# design.net
KiCad netlist of a schematic drawn in Altium Designer
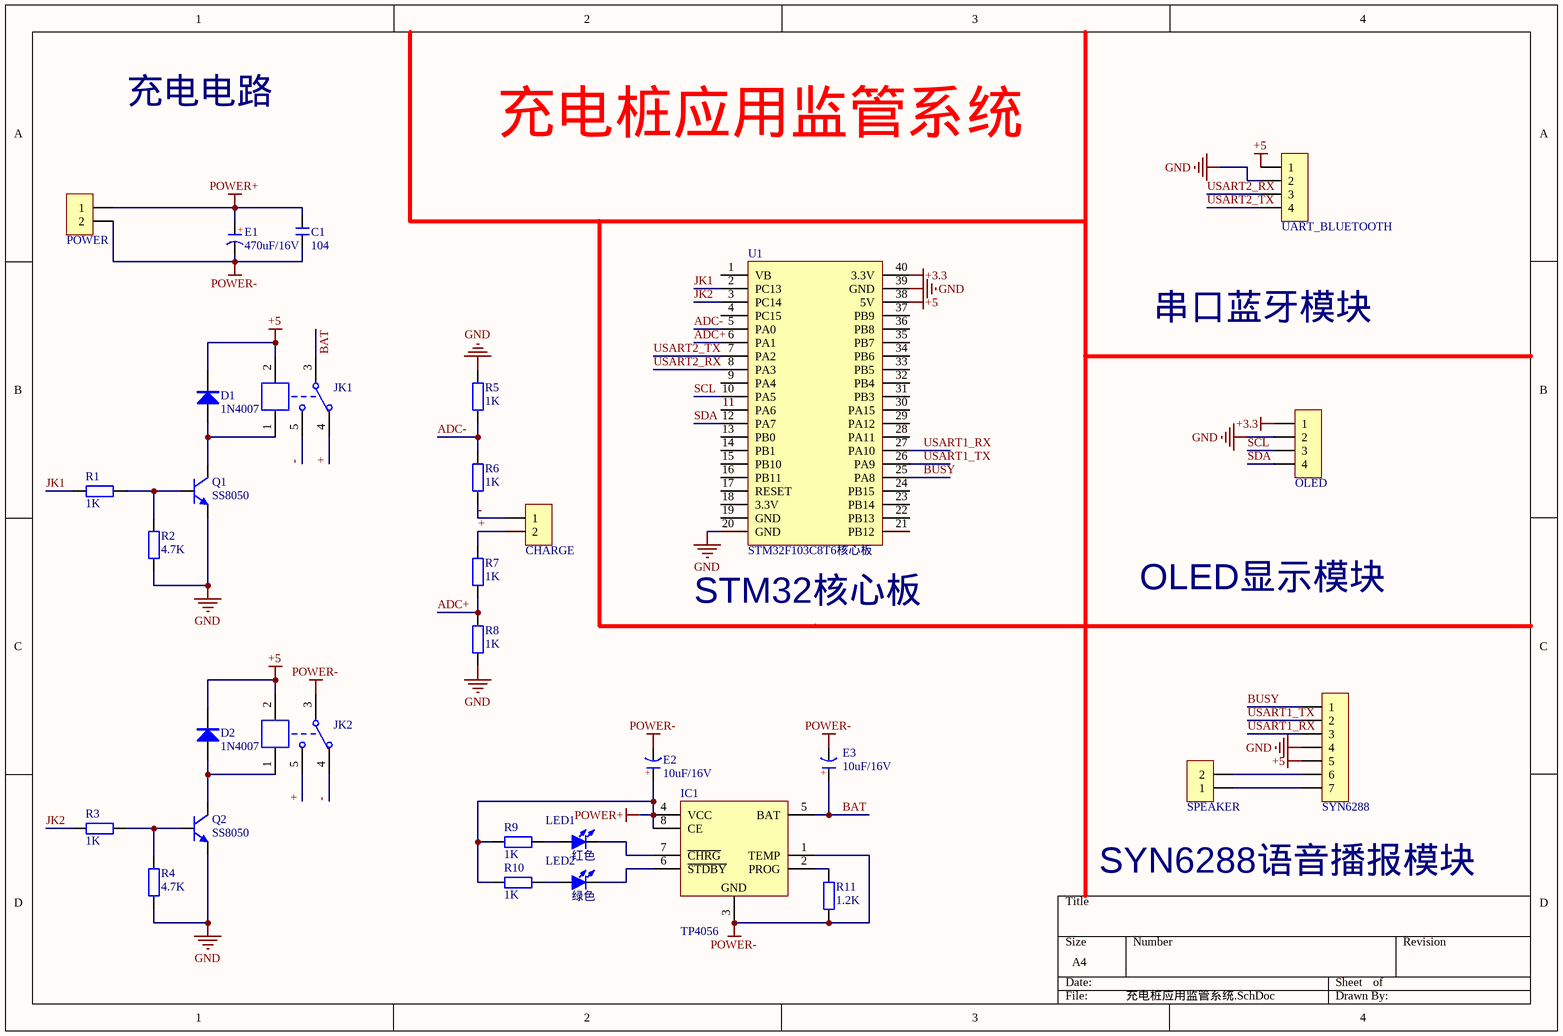
[diagram p0: 充电桩应用监管系统.SchDoc]

(export (version "E")
  (design (tool "Eeschema 10.0.6"))
  (components
    (comp (ref "C1")
      (value "104")
      (footprint "CC 1.8*3.6")
      (description "直插瓷片电容")
      (fields (field (name "版权归属") "源创客"))
      (libsource (lib "3.1   - 电阻-电容-电感") (part "C-CC"))
    )
    (comp (ref "CHARGE")
      (value "HDR-1X2")
      (footprint "KF301-5.0-2P")
      (description "2P接插件")
      (fields (field (name "版权归属") "源创客"))
      (libsource (lib "4.9   - 接插件-脚距5.0") (part "Header 2"))
    )
    (comp (ref "D1")
      (value "1N4007")
      (footprint "DO-41")
      (description "整流二极管")
      (fields (field (name "版权归属") "源创客"))
      (libsource (lib "8.1   - 二极管-整流桥") (part "1N4007"))
    )
    (comp (ref "D2")
      (value "1N4007")
      (footprint "DO-41")
      (description "整流二极管")
      (fields (field (name "版权归属") "源创客"))
      (libsource (lib "8.1   - 二极管-整流桥") (part "1N4007"))
    )
    (comp (ref "E1")
      (value "470uF/16V")
      (footprint "CAP 2.0*5*11")
      (description "直插电解电容")
      (fields (field (name "版权归属") "源创客"))
      (libsource (lib "3.1   - 电阻-电容-电感") (part "C-CAP"))
    )
    (comp (ref "E2")
      (value "10uF/16V")
      (footprint "CAP 1.5*4*8")
      (description "直插电解电容")
      (fields (field (name "版权归属") "源创客"))
      (libsource (lib "3.1   - 电阻-电容-电感") (part "C-CAP"))
    )
    (comp (ref "E3")
      (value "10uF/16V")
      (footprint "CAP 1.5*4*8")
      (description "直插电解电容")
      (fields (field (name "版权归属") "源创客"))
      (libsource (lib "3.1   - 电阻-电容-电感") (part "C-CAP"))
    )
    (comp (ref "IC1")
      (value "TP4056")
      (footprint "SOP8_N")
      (description "锂电池充电管理")
      (fields (field (name "版权归属") "源创客"))
      (libsource (lib "1.3   - 电源类芯片") (part "TP4056"))
    )
    (comp (ref "JK1")
      (value "~")
      (footprint "SRD-C_B")
      (description "5V一组转换")
      (fields (field (name "版权归属") "源创客"))
      (libsource (lib "7.1   - 继电器") (part "SRD-05VDC-SL-C"))
    )
    (comp (ref "JK2")
      (value "~")
      (footprint "SRD-C_B")
      (description "5V一组转换")
      (fields (field (name "版权归属") "源创客"))
      (libsource (lib "7.1   - 继电器") (part "SRD-05VDC-SL-C"))
    )
    (comp (ref "LED1")
      (value "红色")
      (footprint "LED 3MM-B")
      (description "插件LED")
      (fields (field (name "版权归属") "源创客"))
      (libsource (lib "9.1   - LED") (part "LED-3MM"))
    )
    (comp (ref "LED2")
      (value "绿色")
      (footprint "LED 3MM-B")
      (description "插件LED")
      (fields (field (name "版权归属") "源创客"))
      (libsource (lib "9.1   - LED") (part "LED-3MM"))
    )
    (comp (ref "OLED")
      (value "HDR-1X4")
      (footprint "HDR2.54-M-LI-4P")
      (description "4P接插件")
      (fields (field (name "版权归属") "源创客"))
      (libsource (lib "4.5   - 接插件-脚距2.54") (part "Header 4"))
    )
    (comp (ref "POWER")
      (value "HDR-1X2")
      (footprint "KF301-5.0-2P")
      (description "2P接插件")
      (fields (field (name "版权归属") "源创客"))
      (libsource (lib "") (part "Header 2_1"))
    )
    (comp (ref "Q1")
      (value "SS8050")
      (footprint "TO92A")
      (description "高频放大-NPN型")
      (fields (field (name "版权归属") "源创客"))
      (libsource (lib "6.2   - 三极管") (part "8050-DIP"))
    )
    (comp (ref "Q2")
      (value "SS8050")
      (footprint "TO92A")
      (description "高频放大-NPN型")
      (fields (field (name "版权归属") "源创客"))
      (libsource (lib "6.2   - 三极管") (part "8050-DIP"))
    )
    (comp (ref "R1")
      (value "1K")
      (footprint "RS 1/4W")
      (description "直插色环电阻")
      (fields (field (name "版权归属") "源创客"))
      (libsource (lib "3.1   - 电阻-电容-电感") (part "R-CRR"))
    )
    (comp (ref "R2")
      (value "4.7K")
      (footprint "RS 1/4W")
      (description "直插色环电阻")
      (fields (field (name "版权归属") "源创客"))
      (libsource (lib "3.1   - 电阻-电容-电感") (part "R-CRR"))
    )
    (comp (ref "R3")
      (value "1K")
      (footprint "RS 1/4W")
      (description "直插色环电阻")
      (fields (field (name "版权归属") "源创客"))
      (libsource (lib "3.1   - 电阻-电容-电感") (part "R-CRR"))
    )
    (comp (ref "R4")
      (value "4.7K")
      (footprint "RS 1/4W")
      (description "直插色环电阻")
      (fields (field (name "版权归属") "源创客"))
      (libsource (lib "3.1   - 电阻-电容-电感") (part "R-CRR"))
    )
    (comp (ref "R5")
      (value "1K")
      (footprint "RS 1/4W")
      (description "直插色环电阻")
      (fields (field (name "版权归属") "源创客"))
      (libsource (lib "3.1   - 电阻-电容-电感") (part "R-CRR"))
    )
    (comp (ref "R6")
      (value "1K")
      (footprint "RS 1/4W")
      (description "直插色环电阻")
      (fields (field (name "版权归属") "源创客"))
      (libsource (lib "3.1   - 电阻-电容-电感") (part "R-CRR"))
    )
    (comp (ref "R7")
      (value "1K")
      (footprint "RS 1/4W")
      (description "直插色环电阻")
      (fields (field (name "版权归属") "源创客"))
      (libsource (lib "3.1   - 电阻-电容-电感") (part "R-CRR"))
    )
    (comp (ref "R8")
      (value "1K")
      (footprint "RS 1/4W")
      (description "直插色环电阻")
      (fields (field (name "版权归属") "源创客"))
      (libsource (lib "3.1   - 电阻-电容-电感") (part "R-CRR"))
    )
    (comp (ref "R9")
      (value "1K")
      (footprint "RS 1/4W")
      (description "直插色环电阻")
      (fields (field (name "版权归属") "源创客"))
      (libsource (lib "3.1   - 电阻-电容-电感") (part "R-CRR"))
    )
    (comp (ref "R10")
      (value "1K")
      (footprint "RS 1/4W")
      (description "直插色环电阻")
      (fields (field (name "版权归属") "源创客"))
      (libsource (lib "3.1   - 电阻-电容-电感") (part "R-CRR"))
    )
    (comp (ref "R11")
      (value "1.2K")
      (footprint "RS 1/4W")
      (description "直插色环电阻")
      (fields (field (name "版权归属") "源创客"))
      (libsource (lib "3.1   - 电阻-电容-电感") (part "R-CRR"))
    )
    (comp (ref "SPEAKER")
      (value "HDR-1X2")
      (footprint "KF301-5.0-2P")
      (description "2P接插件")
      (fields (field (name "版权归属") "源创客"))
      (libsource (lib "") (part "Header 2_2"))
    )
    (comp (ref "SYN6288")
      (value "HDR-1X7")
      (footprint "PH2.0-LI-7P")
      (description "7P接插件")
      (fields (field (name "版权归属") "源创客"))
      (libsource (lib "4.4   - 接插件-脚距2.0") (part "Header 7"))
    )
    (comp (ref "U1")
      (value "STM32F103C8T6核心板")
      (footprint "DIP_TP40-600")
      (libsource (lib "STM32F103C8T6核心板") (part "STM32F103C8T6核心板"))
    )
    (comp (ref "UART_BLUETOOTH")
      (value "HDR-1X4")
      (footprint "HDR2.54-M-LI-4P")
      (description "4P接插件")
      (fields (field (name "版权归属") "源创客"))
      (libsource (lib "4.5   - 接插件-脚距2.54") (part "Header 4"))
    )
  )
  (nets
    (net (code "1") (name "+3.3") (class "Default")
      (node (ref "OLED") (pin "1") (pinfunction "1_1") (pintype "passive"))
      (node (ref "U1") (pin "40") (pinfunction "3.3V_40") (pintype "passive"))
    )
    (net (code "2") (name "+5") (class "Default")
      (node (ref "D1") (pin "2") (pinfunction "K_2") (pintype "passive"))
      (node (ref "D2") (pin "2") (pinfunction "K_2") (pintype "passive"))
      (node (ref "JK1") (pin "2") (pinfunction "2_2") (pintype "passive"))
      (node (ref "JK2") (pin "2") (pinfunction "2_2") (pintype "passive"))
      (node (ref "SYN6288") (pin "5") (pinfunction "5_5") (pintype "passive"))
      (node (ref "U1") (pin "38") (pinfunction "5V_38") (pintype "passive"))
      (node (ref "UART_BLUETOOTH") (pin "1") (pinfunction "1_1") (pintype "passive"))
    )
    (net (code "3") (name "/+") (class "Default")
      (node (ref "CHARGE") (pin "2") (pinfunction "2_2") (pintype "passive"))
      (node (ref "JK1") (pin "4") (pinfunction "4_4") (pintype "passive"))
      (node (ref "JK2") (pin "5") (pinfunction "5_5") (pintype "passive"))
      (node (ref "R7") (pin "2") (pinfunction "2_2") (pintype "passive"))
    )
    (net (code "4") (name "/-") (class "Default")
      (node (ref "CHARGE") (pin "1") (pinfunction "1_1") (pintype "passive"))
      (node (ref "JK1") (pin "5") (pinfunction "5_5") (pintype "passive"))
      (node (ref "JK2") (pin "4") (pinfunction "4_4") (pintype "passive"))
      (node (ref "R6") (pin "1") (pinfunction "1_1") (pintype "passive"))
    )
    (net (code "5") (name "/ADC+") (class "Default")
      (node (ref "R7") (pin "1") (pinfunction "1_1") (pintype "passive"))
      (node (ref "R8") (pin "2") (pinfunction "2_2") (pintype "passive"))
      (node (ref "U1") (pin "6") (pinfunction "PA1_6") (pintype "passive"))
    )
    (net (code "6") (name "/ADC-") (class "Default")
      (node (ref "R5") (pin "1") (pinfunction "1_1") (pintype "passive"))
      (node (ref "R6") (pin "2") (pinfunction "2_2") (pintype "passive"))
      (node (ref "U1") (pin "5") (pinfunction "PA0_5") (pintype "passive"))
    )
    (net (code "7") (name "/BAT") (class "Default")
      (node (ref "E3") (pin "1") (pinfunction "A_1") (pintype "passive"))
      (node (ref "IC1") (pin "5") (pinfunction "BAT_5") (pintype "passive"))
      (node (ref "JK1") (pin "3") (pinfunction "3_3") (pintype "passive"))
    )
    (net (code "8") (name "/BUSY") (class "Default")
      (node (ref "SYN6288") (pin "1") (pinfunction "1_1") (pintype "passive"))
      (node (ref "U1") (pin "25") (pinfunction "PA8_25") (pintype "passive"))
    )
    (net (code "9") (name "/JK1") (class "Default")
      (node (ref "R1") (pin "1") (pinfunction "1_1") (pintype "passive"))
      (node (ref "U1") (pin "2") (pinfunction "PC13_2") (pintype "passive"))
    )
    (net (code "10") (name "/JK2") (class "Default")
      (node (ref "R3") (pin "1") (pinfunction "1_1") (pintype "passive"))
      (node (ref "U1") (pin "3") (pinfunction "PC14_3") (pintype "passive"))
    )
    (net (code "11") (name "/SCL") (class "Default")
      (node (ref "OLED") (pin "3") (pinfunction "3_3") (pintype "passive"))
      (node (ref "U1") (pin "10") (pinfunction "PA5_10") (pintype "passive"))
    )
    (net (code "12") (name "/SDA") (class "Default")
      (node (ref "OLED") (pin "4") (pinfunction "4_4") (pintype "passive"))
      (node (ref "U1") (pin "12") (pinfunction "PA7_12") (pintype "passive"))
    )
    (net (code "13") (name "/USART1_RX") (class "Default")
      (node (ref "SYN6288") (pin "3") (pinfunction "3_3") (pintype "passive"))
      (node (ref "U1") (pin "27") (pinfunction "PA10_27") (pintype "passive"))
    )
    (net (code "14") (name "/USART1_TX") (class "Default")
      (node (ref "SYN6288") (pin "2") (pinfunction "2_2") (pintype "passive"))
      (node (ref "U1") (pin "26") (pinfunction "PA9_26") (pintype "passive"))
    )
    (net (code "15") (name "/USART2_RX") (class "Default")
      (node (ref "U1") (pin "8") (pinfunction "PA3_8") (pintype "passive"))
      (node (ref "UART_BLUETOOTH") (pin "3") (pinfunction "3_3") (pintype "passive"))
    )
    (net (code "16") (name "/USART2_TX") (class "Default")
      (node (ref "U1") (pin "7") (pinfunction "PA2_7") (pintype "passive"))
      (node (ref "UART_BLUETOOTH") (pin "4") (pinfunction "4_4") (pintype "passive"))
    )
    (net (code "17") (name "GND") (class "Default")
      (node (ref "OLED") (pin "2") (pinfunction "2_2") (pintype "passive"))
      (node (ref "Q1") (pin "1") (pinfunction "E_1") (pintype "passive"))
      (node (ref "Q2") (pin "1") (pinfunction "E_1") (pintype "passive"))
      (node (ref "R2") (pin "1") (pinfunction "1_1") (pintype "passive"))
      (node (ref "R4") (pin "1") (pinfunction "1_1") (pintype "passive"))
      (node (ref "R5") (pin "2") (pinfunction "2_2") (pintype "passive"))
      (node (ref "R8") (pin "1") (pinfunction "1_1") (pintype "passive"))
      (node (ref "SYN6288") (pin "4") (pinfunction "4_4") (pintype "passive"))
      (node (ref "U1") (pin "20") (pinfunction "GND_20") (pintype "passive"))
      (node (ref "U1") (pin "39") (pinfunction "GND_39") (pintype "passive"))
      (node (ref "UART_BLUETOOTH") (pin "2") (pinfunction "2_2") (pintype "passive"))
    )
    (net (code "18") (name "Net-(D1-A)") (class "Default")
      (node (ref "D1") (pin "1") (pinfunction "A_1") (pintype "passive"))
      (node (ref "JK1") (pin "1") (pinfunction "1_1") (pintype "passive"))
      (node (ref "Q1") (pin "3") (pinfunction "C_3") (pintype "passive"))
    )
    (net (code "19") (name "Net-(D2-A)") (class "Default")
      (node (ref "D2") (pin "1") (pinfunction "A_1") (pintype "passive"))
      (node (ref "JK2") (pin "1") (pinfunction "1_1") (pintype "passive"))
      (node (ref "Q2") (pin "3") (pinfunction "C_3") (pintype "passive"))
    )
    (net (code "20") (name "Net-(IC1-PROG)") (class "Default")
      (node (ref "IC1") (pin "2") (pinfunction "PROG_2") (pintype "passive"))
      (node (ref "R11") (pin "2") (pinfunction "2_2") (pintype "passive"))
    )
    (net (code "21") (name "Net-(IC1-~{CHRG})") (class "Default")
      (node (ref "IC1") (pin "7") (pinfunction "~{CHRG}_7") (pintype "passive"))
      (node (ref "LED1") (pin "2") (pinfunction "K_2") (pintype "passive"))
    )
    (net (code "22") (name "Net-(IC1-~{STDBY})") (class "Default")
      (node (ref "IC1") (pin "6") (pinfunction "~{STDBY}_6") (pintype "passive"))
      (node (ref "LED2") (pin "2") (pinfunction "K_2") (pintype "passive"))
    )
    (net (code "23") (name "Net-(LED1-A)") (class "Default")
      (node (ref "LED1") (pin "1") (pinfunction "A_1") (pintype "passive"))
      (node (ref "R9") (pin "2") (pinfunction "2_2") (pintype "passive"))
    )
    (net (code "24") (name "Net-(LED2-A)") (class "Default")
      (node (ref "LED2") (pin "1") (pinfunction "A_1") (pintype "passive"))
      (node (ref "R10") (pin "2") (pinfunction "2_2") (pintype "passive"))
    )
    (net (code "25") (name "Net-(Q1-B)") (class "Default")
      (node (ref "Q1") (pin "2") (pinfunction "B_2") (pintype "passive"))
      (node (ref "R1") (pin "2") (pinfunction "2_2") (pintype "passive"))
      (node (ref "R2") (pin "2") (pinfunction "2_2") (pintype "passive"))
    )
    (net (code "26") (name "Net-(Q2-B)") (class "Default")
      (node (ref "Q2") (pin "2") (pinfunction "B_2") (pintype "passive"))
      (node (ref "R3") (pin "2") (pinfunction "2_2") (pintype "passive"))
      (node (ref "R4") (pin "2") (pinfunction "2_2") (pintype "passive"))
    )
    (net (code "27") (name "Net-(SPEAKER-Pad1)") (class "Default")
      (node (ref "SPEAKER") (pin "1") (pinfunction "1_1") (pintype "passive"))
      (node (ref "SYN6288") (pin "7") (pinfunction "7_7") (pintype "passive"))
    )
    (net (code "28") (name "Net-(SPEAKER-Pad2)") (class "Default")
      (node (ref "SPEAKER") (pin "2") (pinfunction "2_2") (pintype "passive"))
      (node (ref "SYN6288") (pin "6") (pinfunction "6_6") (pintype "passive"))
    )
    (net (code "29") (name "POWER+") (class "Default")
      (node (ref "C1") (pin "1") (pinfunction "1_1") (pintype "passive"))
      (node (ref "E1") (pin "1") (pinfunction "A_1") (pintype "passive"))
      (node (ref "E2") (pin "1") (pinfunction "A_1") (pintype "passive"))
      (node (ref "IC1") (pin "4") (pinfunction "VCC_4") (pintype "passive"))
      (node (ref "IC1") (pin "8") (pinfunction "CE_8") (pintype "passive"))
      (node (ref "POWER") (pin "1") (pinfunction "1_1") (pintype "passive"))
      (node (ref "R10") (pin "1") (pinfunction "1_1") (pintype "passive"))
      (node (ref "R9") (pin "1") (pinfunction "1_1") (pintype "passive"))
    )
    (net (code "30") (name "POWER-") (class "Default")
      (node (ref "C1") (pin "2") (pinfunction "2_2") (pintype "passive"))
      (node (ref "E1") (pin "2") (pinfunction "K_2") (pintype "passive"))
      (node (ref "E2") (pin "2") (pinfunction "K_2") (pintype "passive"))
      (node (ref "E3") (pin "2") (pinfunction "K_2") (pintype "passive"))
      (node (ref "IC1") (pin "1") (pinfunction "TEMP_1") (pintype "passive"))
      (node (ref "IC1") (pin "3") (pinfunction "GND_3") (pintype "passive"))
      (node (ref "JK2") (pin "3") (pinfunction "3_3") (pintype "passive"))
      (node (ref "POWER") (pin "2") (pinfunction "2_2") (pintype "passive"))
      (node (ref "R11") (pin "1") (pinfunction "1_1") (pintype "passive"))
    )
    (net (code "31") (name "unconnected-(U1-3.3V-Pad18)") (class "Default")
      (node (ref "U1") (pin "18") (pinfunction "3.3V_18") (pintype "passive"))
    )
    (net (code "32") (name "unconnected-(U1-GND-Pad19)") (class "Default")
      (node (ref "U1") (pin "19") (pinfunction "GND_19") (pintype "passive"))
    )
    (net (code "33") (name "unconnected-(U1-PA4-Pad9)") (class "Default")
      (node (ref "U1") (pin "9") (pinfunction "PA4_9") (pintype "passive"))
    )
    (net (code "34") (name "unconnected-(U1-PA6-Pad11)") (class "Default")
      (node (ref "U1") (pin "11") (pinfunction "PA6_11") (pintype "passive"))
    )
    (net (code "35") (name "unconnected-(U1-PA11-Pad28)") (class "Default")
      (node (ref "U1") (pin "28") (pinfunction "PA11_28") (pintype "passive"))
    )
    (net (code "36") (name "unconnected-(U1-PA12-Pad29)") (class "Default")
      (node (ref "U1") (pin "29") (pinfunction "PA12_29") (pintype "passive"))
    )
    (net (code "37") (name "unconnected-(U1-PA15-Pad30)") (class "Default")
      (node (ref "U1") (pin "30") (pinfunction "PA15_30") (pintype "passive"))
    )
    (net (code "38") (name "unconnected-(U1-PB0-Pad13)") (class "Default")
      (node (ref "U1") (pin "13") (pinfunction "PB0_13") (pintype "passive"))
    )
    (net (code "39") (name "unconnected-(U1-PB1-Pad14)") (class "Default")
      (node (ref "U1") (pin "14") (pinfunction "PB1_14") (pintype "passive"))
    )
    (net (code "40") (name "unconnected-(U1-PB3-Pad31)") (class "Default")
      (node (ref "U1") (pin "31") (pinfunction "PB3_31") (pintype "passive"))
    )
    (net (code "41") (name "unconnected-(U1-PB4-Pad32)") (class "Default")
      (node (ref "U1") (pin "32") (pinfunction "PB4_32") (pintype "passive"))
    )
    (net (code "42") (name "unconnected-(U1-PB5-Pad33)") (class "Default")
      (node (ref "U1") (pin "33") (pinfunction "PB5_33") (pintype "passive"))
    )
    (net (code "43") (name "unconnected-(U1-PB6-Pad34)") (class "Default")
      (node (ref "U1") (pin "34") (pinfunction "PB6_34") (pintype "passive"))
    )
    (net (code "44") (name "unconnected-(U1-PB7-Pad35)") (class "Default")
      (node (ref "U1") (pin "35") (pinfunction "PB7_35") (pintype "passive"))
    )
    (net (code "45") (name "unconnected-(U1-PB8-Pad36)") (class "Default")
      (node (ref "U1") (pin "36") (pinfunction "PB8_36") (pintype "passive"))
    )
    (net (code "46") (name "unconnected-(U1-PB9-Pad37)") (class "Default")
      (node (ref "U1") (pin "37") (pinfunction "PB9_37") (pintype "passive"))
    )
    (net (code "47") (name "unconnected-(U1-PB10-Pad15)") (class "Default")
      (node (ref "U1") (pin "15") (pinfunction "PB10_15") (pintype "passive"))
    )
    (net (code "48") (name "unconnected-(U1-PB11-Pad16)") (class "Default")
      (node (ref "U1") (pin "16") (pinfunction "PB11_16") (pintype "passive"))
    )
    (net (code "49") (name "unconnected-(U1-PB12-Pad21)") (class "Default")
      (node (ref "U1") (pin "21") (pinfunction "PB12_21") (pintype "passive"))
    )
    (net (code "50") (name "unconnected-(U1-PB13-Pad22)") (class "Default")
      (node (ref "U1") (pin "22") (pinfunction "PB13_22") (pintype "passive"))
    )
    (net (code "51") (name "unconnected-(U1-PB14-Pad23)") (class "Default")
      (node (ref "U1") (pin "23") (pinfunction "PB14_23") (pintype "passive"))
    )
    (net (code "52") (name "unconnected-(U1-PB15-Pad24)") (class "Default")
      (node (ref "U1") (pin "24") (pinfunction "PB15_24") (pintype "passive"))
    )
    (net (code "53") (name "unconnected-(U1-PC15-Pad4)") (class "Default")
      (node (ref "U1") (pin "4") (pinfunction "PC15_4") (pintype "passive"))
    )
    (net (code "54") (name "unconnected-(U1-RESET-Pad17)") (class "Default")
      (node (ref "U1") (pin "17") (pinfunction "RESET_17") (pintype "passive"))
    )
    (net (code "55") (name "unconnected-(U1-VB-Pad1)") (class "Default")
      (node (ref "U1") (pin "1") (pinfunction "VB_1") (pintype "passive"))
    )
  )
)
